# ACC_ICM20948.net
KiCad netlist of a schematic drawn in Altium Designer
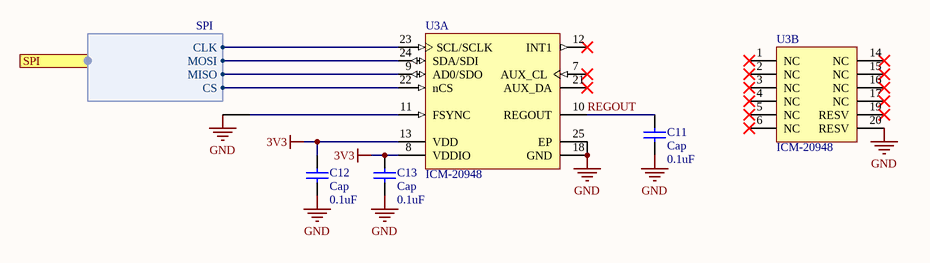
[diagram p0: ACC_ICM20948.SchDoc]

(export (version "E")
  (design (tool "Eeschema 10.0.6"))
  (components
    (comp (ref "C11")
      (value "Cap")
      (footprint "CAPC1005N")
      (description "Capacitor")
      (fields (field (name "ALTIUM_VALUE") "0.1uF") (field (name "PUBLISHER") "Altium Limited"))
      (libsource (lib "Miscellaneous Devices") (part "Cap"))
    )
    (comp (ref "C12")
      (value "Cap")
      (footprint "CAPC1005N")
      (description "Capacitor")
      (fields (field (name "ALTIUM_VALUE") "0.1uF") (field (name "PUBLISHER") "Altium Limited"))
      (libsource (lib "Miscellaneous Devices") (part "Cap"))
    )
    (comp (ref "C13")
      (value "Cap")
      (footprint "CAPC1005N")
      (description "Capacitor")
      (fields (field (name "ALTIUM_VALUE") "0.1uF") (field (name "PUBLISHER") "Altium Limited"))
      (libsource (lib "Miscellaneous Devices") (part "Cap"))
    )
    (comp (ref "U3")
      (value "ICM-20948")
      (footprint "TDK-QFN-24_M")
      (fields (field (name "MANUFACTURER") "TDK"))
      (libsource (lib "Altium Content Vault") (part "TDK-ICM-20948-QFN-24"))
    )
  )
  (nets
    (net (code "2") (name "/CLK") (class "Default")
      (node (ref "U3") (pin "23") (pinfunction "SCL/SCLK_23") (pintype "input"))
    )
    (net (code "3") (name "/CS") (class "Default")
      (node (ref "U3") (pin "22") (pinfunction "nCS_22") (pintype "input"))
    )
    (net (code "4") (name "/MISO") (class "Default")
      (node (ref "U3") (pin "9") (pinfunction "AD0/SDO_9") (pintype "bidirectional"))
    )
    (net (code "5") (name "/MOSI") (class "Default")
      (node (ref "U3") (pin "24") (pinfunction "SDA/SDI_24") (pintype "bidirectional"))
    )
    (net (code "6") (name "/REGOUT") (class "Default")
      (node (ref "C11") (pin "2") (pinfunction "2_2") (pintype "passive"))
      (node (ref "U3") (pin "10") (pinfunction "REGOUT_10") (pintype "passive"))
    )
    (net (code "8") (name "3V3") (class "Default")
      (node (ref "C12") (pin "2") (pinfunction "2_2") (pintype "passive"))
      (node (ref "C13") (pin "2") (pinfunction "2_2") (pintype "passive"))
      (node (ref "U3") (pin "13") (pinfunction "VDD_13") (pintype "power_in"))
      (node (ref "U3") (pin "8") (pinfunction "VDDIO_8") (pintype "power_in"))
    )
    (net (code "9") (name "GND") (class "Default")
      (node (ref "C11") (pin "1") (pinfunction "1_1") (pintype "passive"))
      (node (ref "C12") (pin "1") (pinfunction "1_1") (pintype "passive"))
      (node (ref "C13") (pin "1") (pinfunction "1_1") (pintype "passive"))
      (node (ref "U3") (pin "11") (pinfunction "FSYNC_11") (pintype "input"))
      (node (ref "U3") (pin "18") (pinfunction "GND_18") (pintype "power_in"))
      (node (ref "U3") (pin "20") (pinfunction "RESV_20") (pintype "passive"))
      (node (ref "U3") (pin "25") (pinfunction "EP_25") (pintype "passive"))
    )
    (net (code "10") (name "unconnected-(U3A-AUX_CL-Pad7)") (class "Default")
      (node (ref "U3") (pin "7") (pinfunction "AUX_CL_7") (pintype "input+no_connect"))
    )
    (net (code "11") (name "unconnected-(U3A-AUX_DA-Pad21)") (class "Default")
      (node (ref "U3") (pin "21") (pinfunction "AUX_DA_21") (pintype "passive+no_connect"))
    )
    (net (code "12") (name "unconnected-(U3A-INT1-Pad12)") (class "Default")
      (node (ref "U3") (pin "12") (pinfunction "INT1_12") (pintype "output+no_connect"))
    )
    (net (code "13") (name "unconnected-(U3B-NC-Pad1)") (class "Default")
      (node (ref "U3") (pin "1") (pinfunction "NC_1") (pintype "passive+no_connect"))
    )
    (net (code "14") (name "unconnected-(U3B-NC-Pad2)") (class "Default")
      (node (ref "U3") (pin "2") (pinfunction "NC_2") (pintype "passive+no_connect"))
    )
    (net (code "15") (name "unconnected-(U3B-NC-Pad3)") (class "Default")
      (node (ref "U3") (pin "3") (pinfunction "NC_3") (pintype "passive+no_connect"))
    )
    (net (code "16") (name "unconnected-(U3B-NC-Pad4)") (class "Default")
      (node (ref "U3") (pin "4") (pinfunction "NC_4") (pintype "passive+no_connect"))
    )
    (net (code "17") (name "unconnected-(U3B-NC-Pad5)") (class "Default")
      (node (ref "U3") (pin "5") (pinfunction "NC_5") (pintype "passive+no_connect"))
    )
    (net (code "18") (name "unconnected-(U3B-NC-Pad6)") (class "Default")
      (node (ref "U3") (pin "6") (pinfunction "NC_6") (pintype "passive+no_connect"))
    )
    (net (code "19") (name "unconnected-(U3B-NC-Pad14)") (class "Default")
      (node (ref "U3") (pin "14") (pinfunction "NC_14") (pintype "passive+no_connect"))
    )
    (net (code "20") (name "unconnected-(U3B-NC-Pad15)") (class "Default")
      (node (ref "U3") (pin "15") (pinfunction "NC_15") (pintype "passive+no_connect"))
    )
    (net (code "21") (name "unconnected-(U3B-NC-Pad16)") (class "Default")
      (node (ref "U3") (pin "16") (pinfunction "NC_16") (pintype "passive+no_connect"))
    )
    (net (code "22") (name "unconnected-(U3B-NC-Pad17)") (class "Default")
      (node (ref "U3") (pin "17") (pinfunction "NC_17") (pintype "passive+no_connect"))
    )
    (net (code "23") (name "unconnected-(U3B-RESV-Pad19)") (class "Default")
      (node (ref "U3") (pin "19") (pinfunction "RESV_19") (pintype "passive+no_connect"))
    )
  )
)
